# 07-N100.net
KiCad netlist of a schematic drawn in Altium Designer
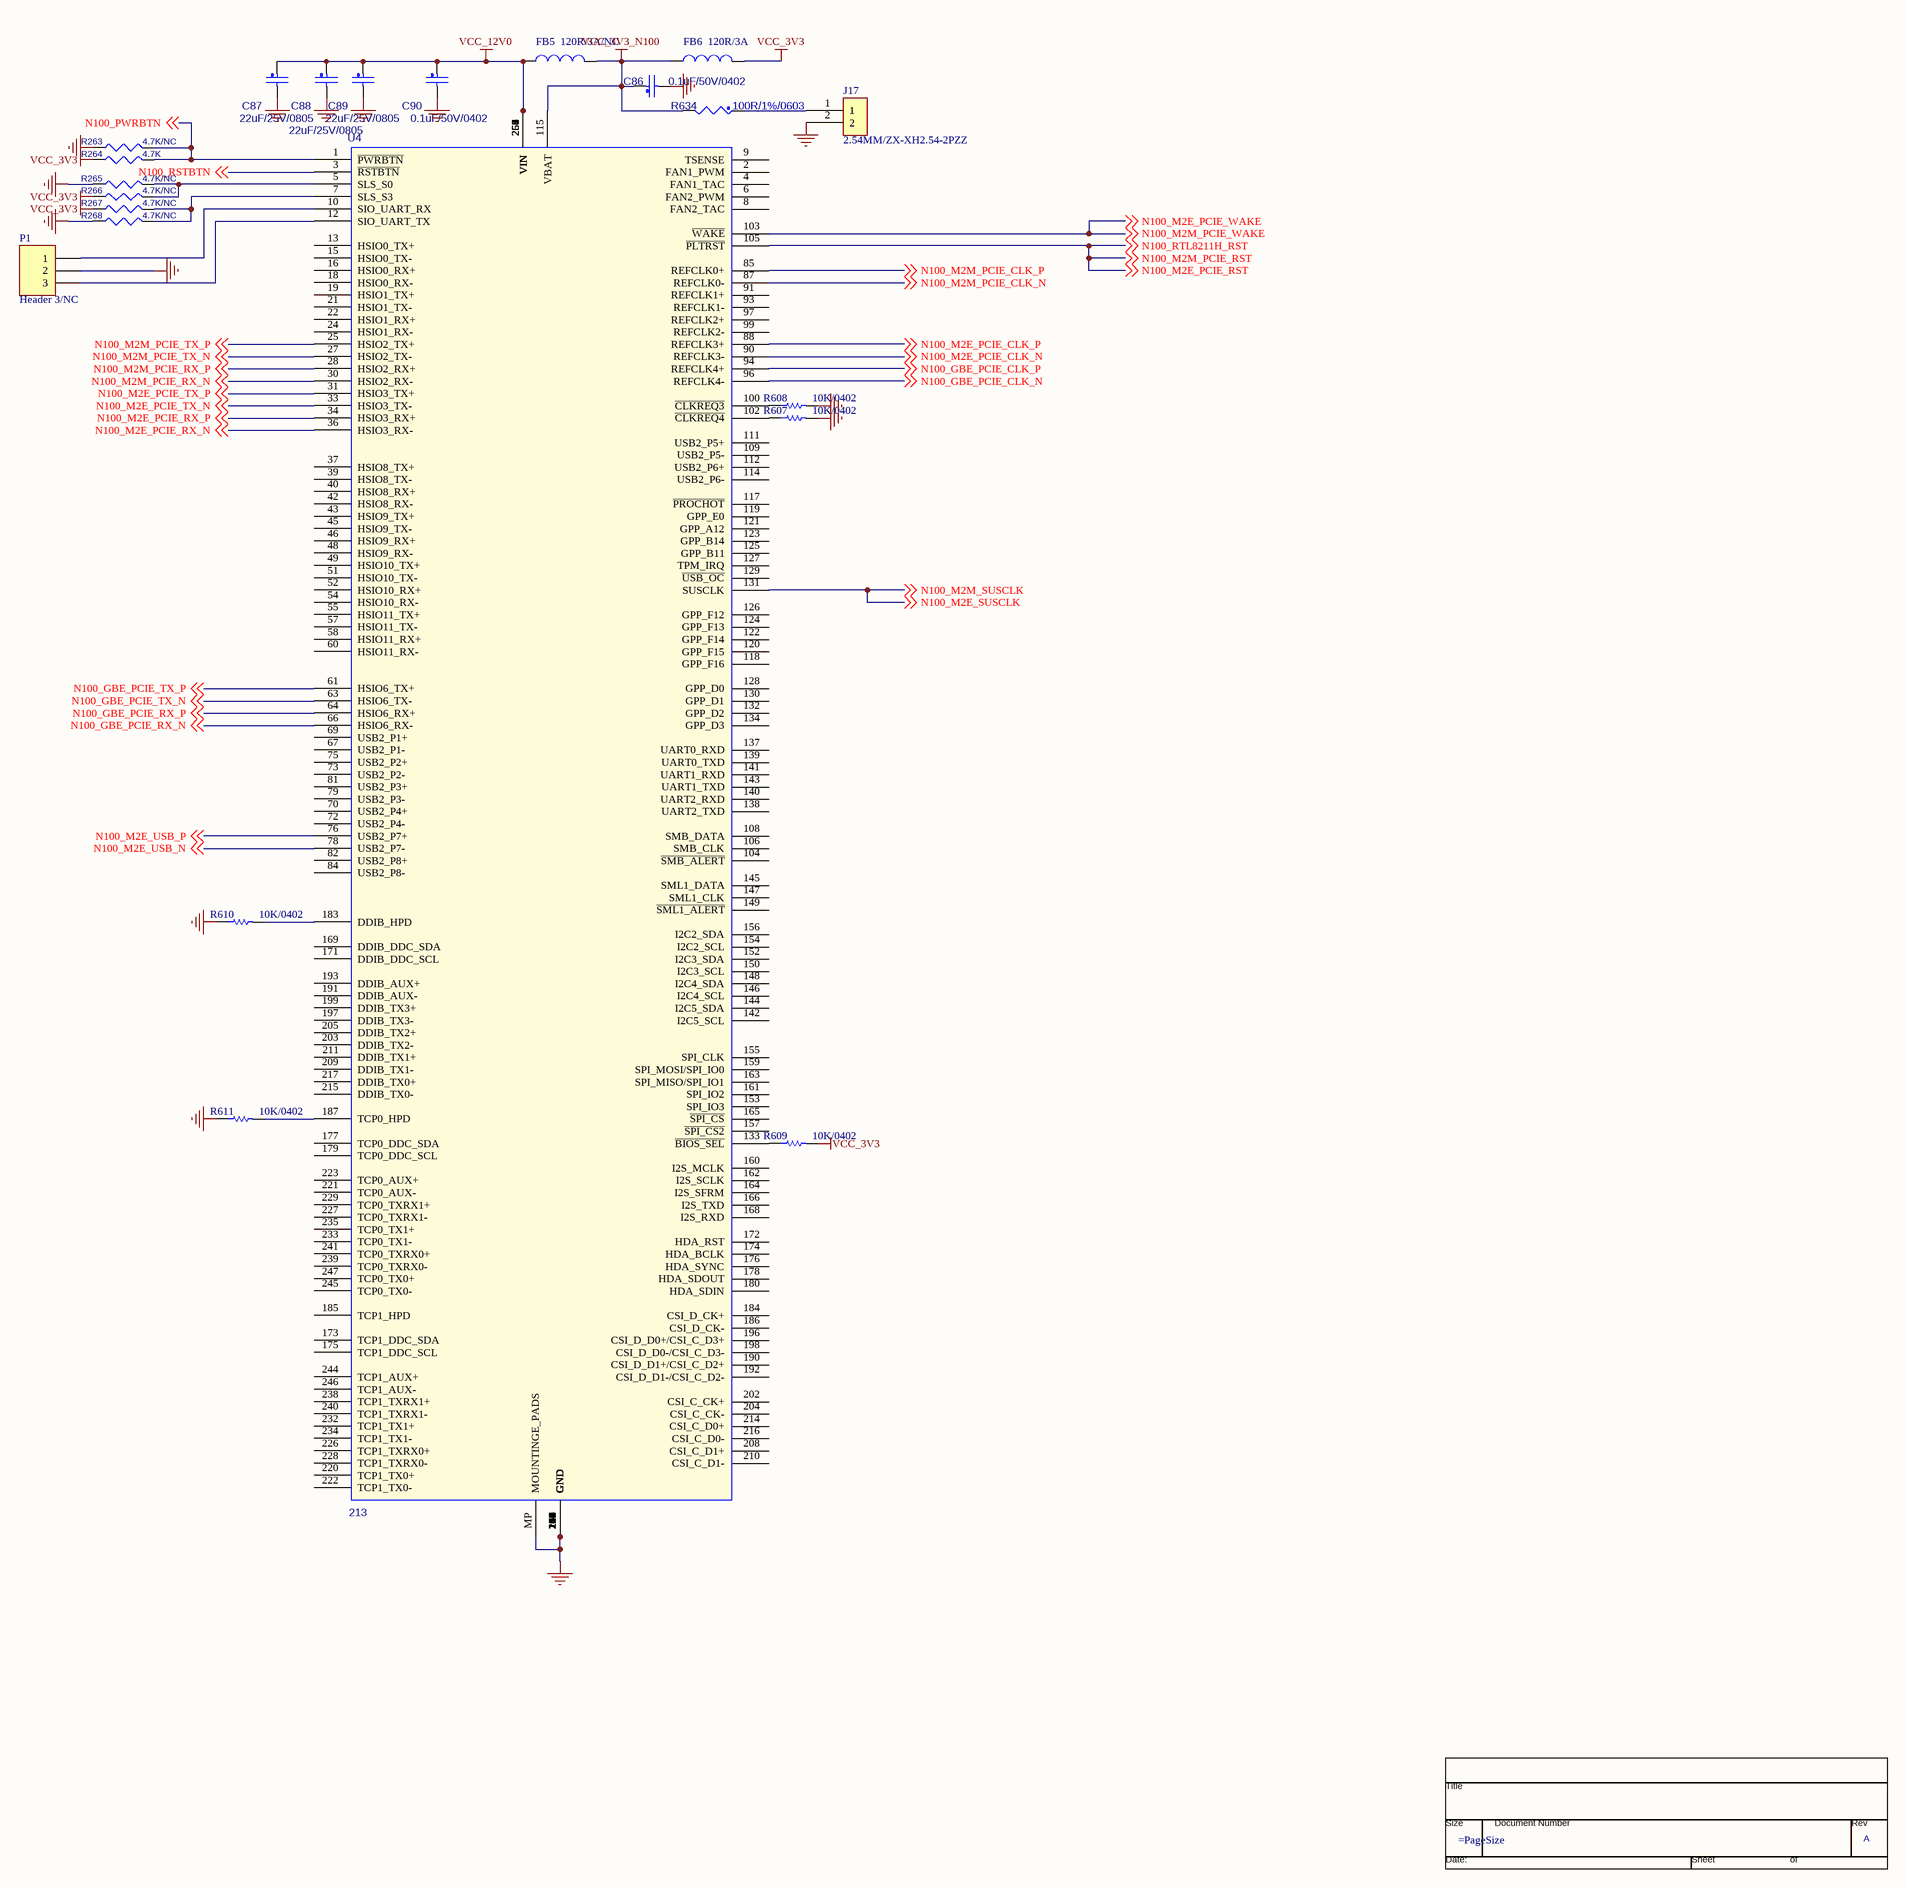
[diagram p0: 07-N100.SchDoc]

(export (version "E")
  (design (tool "Eeschema 10.0.6"))
  (components
    (comp (ref "C86")
      (value "0.1uF/50V/0402")
      (footprint "C0402")
      (description "GCM155R71H104KE02/MURATA")
      (fields (field (name "TOLERANCE") "10%") (field (name "VOLTAGE") "16V"))
      (libsource (lib "*") (part "CAP_NP"))
    )
    (comp (ref "C87")
      (value "22uF/25V/0805")
      (footprint "C0805")
      (description "GRT31CC71E226ME13/MURATA")
      (fields (field (name "VOLTAGE") "10v") (field (name "TOLERANCE") "10%"))
      (libsource (lib "*") (part "CAP_NP"))
    )
    (comp (ref "C88")
      (value "22uF/25V/0805")
      (footprint "C0805")
      (description "GRT31CC71E226ME13/MURATA")
      (fields (field (name "VOLTAGE") "10v") (field (name "TOLERANCE") "10%"))
      (libsource (lib "*") (part "CAP_NP"))
    )
    (comp (ref "C89")
      (value "22uF/25V/0805")
      (footprint "C0805")
      (description "GRT31CC71E226ME13/MURATA")
      (fields (field (name "VOLTAGE") "10v") (field (name "TOLERANCE") "10%"))
      (libsource (lib "*") (part "CAP_NP"))
    )
    (comp (ref "C90")
      (value "0.1uF/50V/0402")
      (footprint "C0402")
      (description "GCM155R71H104KE02/MURATA")
      (fields (field (name "TOLERANCE") "10%") (field (name "VOLTAGE") "16V"))
      (libsource (lib "*") (part "CAP_NP"))
    )
    (comp (ref "FB5")
      (value "120R/3A/NC")
      (footprint "L0603")
      (description "BLM18KG121TN1D")
      (fields (field (name "PUBLISHER") "Altium Limited"))
      (libsource (lib "LIBS") (part "Inductor"))
    )
    (comp (ref "FB6")
      (value "120R/3A")
      (footprint "L0603")
      (description "BLM18KG121TN1D")
      (fields (field (name "PUBLISHER") "Altium Limited"))
      (libsource (lib "LIBS") (part "Inductor"))
    )
    (comp (ref "J17")
      (value "2.54MM/ZX-XH2.54-2PZZ")
      (footprint "CONN-TH_2P-P2.50_HX25003-2A")
      (libsource (lib "LIBS") (part "header2"))
    )
    (comp (ref "P1")
      (value "Header 3/NC")
      (footprint "HEADER3")
      (description "Header, 3-Pin")
      (fields (field (name "PUBLISHER") "Altium Limited"))
      (libsource (lib "LIBS") (part "Header 3"))
    )
    (comp (ref "R263")
      (value "4.7K/NC")
      (footprint "R0402")
      (fields (field (name "Comment") "RESISTOR"))
      (libsource (lib "*") (part "RESISTOR"))
    )
    (comp (ref "R264")
      (value "4.7K")
      (footprint "R0402")
      (fields (field (name "Comment") "RESISTOR"))
      (libsource (lib "*") (part "RESISTOR"))
    )
    (comp (ref "R265")
      (value "4.7K/NC")
      (footprint "R0402")
      (fields (field (name "Comment") "RESISTOR"))
      (libsource (lib "*") (part "RESISTOR"))
    )
    (comp (ref "R266")
      (value "4.7K/NC")
      (footprint "R0402")
      (fields (field (name "Comment") "RESISTOR"))
      (libsource (lib "*") (part "RESISTOR"))
    )
    (comp (ref "R267")
      (value "4.7K/NC")
      (footprint "R0402")
      (fields (field (name "Comment") "RESISTOR"))
      (libsource (lib "*") (part "RESISTOR"))
    )
    (comp (ref "R268")
      (value "4.7K/NC")
      (footprint "R0402")
      (fields (field (name "Comment") "RESISTOR"))
      (libsource (lib "*") (part "RESISTOR"))
    )
    (comp (ref "R607")
      (value "10K/0402")
      (footprint "R0402")
      (description "Semiconductor Resistor")
      (fields (field (name "PUBLISHER") "Altium Limited"))
      (libsource (lib "LIBS") (part "Res Semi"))
    )
    (comp (ref "R608")
      (value "10K/0402")
      (footprint "R0402")
      (description "Semiconductor Resistor")
      (fields (field (name "PUBLISHER") "Altium Limited"))
      (libsource (lib "LIBS") (part "Res Semi"))
    )
    (comp (ref "R609")
      (value "10K/0402")
      (footprint "R0402")
      (description "Semiconductor Resistor")
      (fields (field (name "PUBLISHER") "Altium Limited"))
      (libsource (lib "LIBS") (part "Res Semi"))
    )
    (comp (ref "R610")
      (value "10K/0402")
      (footprint "R0402")
      (description "Semiconductor Resistor")
      (fields (field (name "PUBLISHER") "Altium Limited"))
      (libsource (lib "LIBS") (part "Res Semi"))
    )
    (comp (ref "R611")
      (value "10K/0402")
      (footprint "R0402")
      (description "Semiconductor Resistor")
      (fields (field (name "PUBLISHER") "Altium Limited"))
      (libsource (lib "LIBS") (part "Res Semi"))
    )
    (comp (ref "R634")
      (value "100R/1%/0603")
      (footprint "R0603")
      (description "AC0402FR-070RL/YAGEO")
      (fields (field (name "TOLERANCE") "1%") (field (name "Comment") "RES_Dup2"))
      (libsource (lib "*") (part "RES_Dup2"))
    )
    (comp (ref "U4")
      (value "213")
      (footprint "N100")
      (fields (field (name "Comment") "N100"))
      (libsource (lib "LIBS") (part "N100"))
    )
  )
  (nets
    (net (code "1") (name "GND") (class "Default")
      (node (ref "C86") (pin "2") (pinfunction "2_2") (pintype "passive"))
      (node (ref "C87") (pin "2") (pinfunction "2_2") (pintype "passive"))
      (node (ref "C88") (pin "2") (pinfunction "2_2") (pintype "passive"))
      (node (ref "C89") (pin "2") (pinfunction "2_2") (pintype "passive"))
      (node (ref "C90") (pin "2") (pinfunction "2_2") (pintype "passive"))
      (node (ref "J17") (pin "2") (pinfunction "2_2") (pintype "passive"))
      (node (ref "P1") (pin "2") (pinfunction "2_2") (pintype "passive"))
      (node (ref "R263") (pin "1") (pinfunction "1_1") (pintype "passive"))
      (node (ref "R265") (pin "1") (pinfunction "1_1") (pintype "passive"))
      (node (ref "R268") (pin "1") (pinfunction "1_1") (pintype "passive"))
      (node (ref "R607") (pin "2") (pinfunction "2_2") (pintype "passive"))
      (node (ref "R608") (pin "2") (pinfunction "2_2") (pintype "passive"))
      (node (ref "R610") (pin "1") (pinfunction "1_1") (pintype "passive"))
      (node (ref "R611") (pin "1") (pinfunction "1_1") (pintype "passive"))
      (node (ref "U4") (pin "101") (pinfunction "GND_101") (pintype "passive"))
      (node (ref "U4") (pin "107") (pinfunction "GND_107") (pintype "passive"))
      (node (ref "U4") (pin "11") (pinfunction "GND_11") (pintype "passive"))
      (node (ref "U4") (pin "110") (pinfunction "GND_110") (pintype "passive"))
      (node (ref "U4") (pin "113") (pinfunction "GND_113") (pintype "passive"))
      (node (ref "U4") (pin "116") (pinfunction "GND_116") (pintype "passive"))
      (node (ref "U4") (pin "135") (pinfunction "GND_135") (pintype "passive"))
      (node (ref "U4") (pin "136") (pinfunction "GND_136") (pintype "passive"))
      (node (ref "U4") (pin "14") (pinfunction "GND_14") (pintype "passive"))
      (node (ref "U4") (pin "151") (pinfunction "GND_151") (pintype "passive"))
      (node (ref "U4") (pin "158") (pinfunction "GND_158") (pintype "passive"))
      (node (ref "U4") (pin "167") (pinfunction "GND_167") (pintype "passive"))
      (node (ref "U4") (pin "17") (pinfunction "GND_17") (pintype "passive"))
      (node (ref "U4") (pin "170") (pinfunction "GND_170") (pintype "passive"))
      (node (ref "U4") (pin "181") (pinfunction "GND_181") (pintype "passive"))
      (node (ref "U4") (pin "182") (pinfunction "GND_182") (pintype "passive"))
      (node (ref "U4") (pin "188") (pinfunction "GND_188") (pintype "passive"))
      (node (ref "U4") (pin "189") (pinfunction "GND_189") (pintype "passive"))
      (node (ref "U4") (pin "194") (pinfunction "GND_194") (pintype "passive"))
      (node (ref "U4") (pin "195") (pinfunction "GND_195") (pintype "passive"))
      (node (ref "U4") (pin "20") (pinfunction "GND_20") (pintype "passive"))
      (node (ref "U4") (pin "200") (pinfunction "GND_200") (pintype "passive"))
      (node (ref "U4") (pin "201") (pinfunction "GND_201") (pintype "passive"))
      (node (ref "U4") (pin "206") (pinfunction "GND_206") (pintype "passive"))
      (node (ref "U4") (pin "207") (pinfunction "GND_207") (pintype "passive"))
      (node (ref "U4") (pin "212") (pinfunction "GND_212") (pintype "passive"))
      (node (ref "U4") (pin "213") (pinfunction "GND_213") (pintype "passive"))
      (node (ref "U4") (pin "218") (pinfunction "GND_218") (pintype "passive"))
      (node (ref "U4") (pin "219") (pinfunction "GND_219") (pintype "passive"))
      (node (ref "U4") (pin "224") (pinfunction "GND_224") (pintype "passive"))
      (node (ref "U4") (pin "225") (pinfunction "GND_225") (pintype "passive"))
      (node (ref "U4") (pin "23") (pinfunction "GND_23") (pintype "passive"))
      (node (ref "U4") (pin "230") (pinfunction "GND_230") (pintype "passive"))
      (node (ref "U4") (pin "231") (pinfunction "GND_231") (pintype "passive"))
      (node (ref "U4") (pin "236") (pinfunction "GND_236") (pintype "passive"))
      (node (ref "U4") (pin "237") (pinfunction "GND_237") (pintype "passive"))
      (node (ref "U4") (pin "242") (pinfunction "GND_242") (pintype "passive"))
      (node (ref "U4") (pin "243") (pinfunction "GND_243") (pintype "passive"))
      (node (ref "U4") (pin "248") (pinfunction "GND_248") (pintype "passive"))
      (node (ref "U4") (pin "249") (pinfunction "GND_249") (pintype "passive"))
      (node (ref "U4") (pin "26") (pinfunction "GND_26") (pintype "passive"))
      (node (ref "U4") (pin "29") (pinfunction "GND_29") (pintype "passive"))
      (node (ref "U4") (pin "32") (pinfunction "GND_32") (pintype "passive"))
      (node (ref "U4") (pin "35") (pinfunction "GND_35") (pintype "passive"))
      (node (ref "U4") (pin "38") (pinfunction "GND_38") (pintype "passive"))
      (node (ref "U4") (pin "41") (pinfunction "GND_41") (pintype "passive"))
      (node (ref "U4") (pin "44") (pinfunction "GND_44") (pintype "passive"))
      (node (ref "U4") (pin "47") (pinfunction "GND_47") (pintype "passive"))
      (node (ref "U4") (pin "50") (pinfunction "GND_50") (pintype "passive"))
      (node (ref "U4") (pin "53") (pinfunction "GND_53") (pintype "passive"))
      (node (ref "U4") (pin "56") (pinfunction "GND_56") (pintype "passive"))
      (node (ref "U4") (pin "59") (pinfunction "GND_59") (pintype "passive"))
      (node (ref "U4") (pin "62") (pinfunction "GND_62") (pintype "passive"))
      (node (ref "U4") (pin "65") (pinfunction "GND_65") (pintype "passive"))
      (node (ref "U4") (pin "68") (pinfunction "GND_68") (pintype "passive"))
      (node (ref "U4") (pin "71") (pinfunction "GND_71") (pintype "passive"))
      (node (ref "U4") (pin "74") (pinfunction "GND_74") (pintype "passive"))
      (node (ref "U4") (pin "77") (pinfunction "GND_77") (pintype "passive"))
      (node (ref "U4") (pin "80") (pinfunction "GND_80") (pintype "passive"))
      (node (ref "U4") (pin "83") (pinfunction "GND_83") (pintype "passive"))
      (node (ref "U4") (pin "86") (pinfunction "GND_86") (pintype "passive"))
      (node (ref "U4") (pin "89") (pinfunction "GND_89") (pintype "passive"))
      (node (ref "U4") (pin "92") (pinfunction "GND_92") (pintype "passive"))
      (node (ref "U4") (pin "95") (pinfunction "GND_95") (pintype "passive"))
      (node (ref "U4") (pin "98") (pinfunction "GND_98") (pintype "passive"))
      (node (ref "U4") (pin "MP") (pinfunction "MOUNTINGE_PADS_MP") (pintype "passive"))
    )
    (net (code "2") (name "N100_GBE_PCIE_CLK_N") (class "Default")
      (node (ref "U4") (pin "96") (pinfunction "REFCLK4-_96") (pintype "passive"))
    )
    (net (code "3") (name "N100_GBE_PCIE_CLK_P") (class "Default")
      (node (ref "U4") (pin "94") (pinfunction "REFCLK4+_94") (pintype "passive"))
    )
    (net (code "4") (name "N100_GBE_PCIE_RX_N") (class "Default")
      (node (ref "U4") (pin "66") (pinfunction "HSIO6_RX-_66") (pintype "passive"))
    )
    (net (code "5") (name "N100_GBE_PCIE_RX_P") (class "Default")
      (node (ref "U4") (pin "64") (pinfunction "HSIO6_RX+_64") (pintype "passive"))
    )
    (net (code "6") (name "N100_GBE_PCIE_TX_N") (class "Default")
      (node (ref "U4") (pin "63") (pinfunction "HSIO6_TX-_63") (pintype "passive"))
    )
    (net (code "7") (name "N100_GBE_PCIE_TX_P") (class "Default")
      (node (ref "U4") (pin "61") (pinfunction "HSIO6_TX+_61") (pintype "passive"))
    )
    (net (code "8") (name "N100_M2E_PCIE_CLK_N") (class "Default")
      (node (ref "U4") (pin "90") (pinfunction "REFCLK3-_90") (pintype "passive"))
    )
    (net (code "9") (name "N100_M2E_PCIE_CLK_P") (class "Default")
      (node (ref "U4") (pin "88") (pinfunction "REFCLK3+_88") (pintype "passive"))
    )
    (net (code "10") (name "N100_M2E_PCIE_RST") (class "Default")
      (node (ref "U4") (pin "105") (pinfunction "~{PLTRST}_105") (pintype "passive"))
    )
    (net (code "11") (name "N100_M2E_PCIE_RX_N") (class "Default")
      (node (ref "U4") (pin "36") (pinfunction "HSIO3_RX-_36") (pintype "passive"))
    )
    (net (code "12") (name "N100_M2E_PCIE_RX_P") (class "Default")
      (node (ref "U4") (pin "34") (pinfunction "HSIO3_RX+_34") (pintype "passive"))
    )
    (net (code "13") (name "N100_M2E_PCIE_TX_N") (class "Default")
      (node (ref "U4") (pin "33") (pinfunction "HSIO3_TX-_33") (pintype "passive"))
    )
    (net (code "14") (name "N100_M2E_PCIE_TX_P") (class "Default")
      (node (ref "U4") (pin "31") (pinfunction "HSIO3_TX+_31") (pintype "passive"))
    )
    (net (code "15") (name "N100_M2E_PCIE_WAKE") (class "Default")
      (node (ref "U4") (pin "103") (pinfunction "~{WAKE}_103") (pintype "passive"))
    )
    (net (code "16") (name "N100_M2E_SUSCLK") (class "Default")
      (node (ref "U4") (pin "131") (pinfunction "SUSCLK_131") (pintype "passive"))
    )
    (net (code "17") (name "N100_M2E_USB_N") (class "Default")
      (node (ref "U4") (pin "78") (pinfunction "USB2_P7-_78") (pintype "passive"))
    )
    (net (code "18") (name "N100_M2E_USB_P") (class "Default")
      (node (ref "U4") (pin "76") (pinfunction "USB2_P7+_76") (pintype "passive"))
    )
    (net (code "19") (name "N100_M2M_PCIE_CLK_N") (class "Default")
      (node (ref "U4") (pin "87") (pinfunction "REFCLK0-_87") (pintype "passive"))
    )
    (net (code "20") (name "N100_M2M_PCIE_CLK_P") (class "Default")
      (node (ref "U4") (pin "85") (pinfunction "REFCLK0+_85") (pintype "passive"))
    )
    (net (code "21") (name "N100_M2M_PCIE_RX_N") (class "Default")
      (node (ref "U4") (pin "30") (pinfunction "HSIO2_RX-_30") (pintype "passive"))
    )
    (net (code "22") (name "N100_M2M_PCIE_RX_P") (class "Default")
      (node (ref "U4") (pin "28") (pinfunction "HSIO2_RX+_28") (pintype "passive"))
    )
    (net (code "23") (name "N100_M2M_PCIE_TX_N") (class "Default")
      (node (ref "U4") (pin "27") (pinfunction "HSIO2_TX-_27") (pintype "passive"))
    )
    (net (code "24") (name "N100_M2M_PCIE_TX_P") (class "Default")
      (node (ref "U4") (pin "25") (pinfunction "HSIO2_TX+_25") (pintype "passive"))
    )
    (net (code "25") (name "N100_PWRBTN") (class "Default")
      (node (ref "R263") (pin "2") (pinfunction "2_2") (pintype "passive"))
      (node (ref "R264") (pin "2") (pinfunction "2_2") (pintype "passive"))
      (node (ref "U4") (pin "1") (pinfunction "~{PWRBTN}_1") (pintype "passive"))
    )
    (net (code "26") (name "N100_RSTBTN") (class "Default")
      (node (ref "U4") (pin "3") (pinfunction "~{RSTBTN}_3") (pintype "passive"))
    )
    (net (code "27") (name "Net-(J17-Pad1)") (class "Default")
      (node (ref "J17") (pin "1") (pinfunction "1_1") (pintype "passive"))
      (node (ref "R634") (pin "1") (pinfunction "1_1") (pintype "passive"))
    )
    (net (code "28") (name "Net-(U4-DDIB_HPD)") (class "Default")
      (node (ref "R610") (pin "2") (pinfunction "2_2") (pintype "passive"))
      (node (ref "U4") (pin "183") (pinfunction "DDIB_HPD_183") (pintype "passive"))
    )
    (net (code "29") (name "Net-(U4-SIO_UART_RX)") (class "Default")
      (node (ref "P1") (pin "1") (pinfunction "1_1") (pintype "passive"))
      (node (ref "U4") (pin "10") (pinfunction "SIO_UART_RX_10") (pintype "passive"))
    )
    (net (code "30") (name "Net-(U4-SIO_UART_TX)") (class "Default")
      (node (ref "P1") (pin "3") (pinfunction "3_3") (pintype "passive"))
      (node (ref "U4") (pin "12") (pinfunction "SIO_UART_TX_12") (pintype "passive"))
    )
    (net (code "31") (name "Net-(U4-SLS_S0)") (class "Default")
      (node (ref "R265") (pin "2") (pinfunction "2_2") (pintype "passive"))
      (node (ref "R266") (pin "2") (pinfunction "2_2") (pintype "passive"))
      (node (ref "U4") (pin "5") (pinfunction "SLS_S0_5") (pintype "passive"))
    )
    (net (code "32") (name "Net-(U4-SLS_S3)") (class "Default")
      (node (ref "R267") (pin "2") (pinfunction "2_2") (pintype "passive"))
      (node (ref "R268") (pin "2") (pinfunction "2_2") (pintype "passive"))
      (node (ref "U4") (pin "7") (pinfunction "SLS_S3_7") (pintype "passive"))
    )
    (net (code "33") (name "Net-(U4-TCP0_HPD)") (class "Default")
      (node (ref "R611") (pin "2") (pinfunction "2_2") (pintype "passive"))
      (node (ref "U4") (pin "187") (pinfunction "TCP0_HPD_187") (pintype "passive"))
    )
    (net (code "34") (name "Net-(U4-~{BIOS_SEL})") (class "Default")
      (node (ref "R609") (pin "1") (pinfunction "1_1") (pintype "passive"))
      (node (ref "U4") (pin "133") (pinfunction "~{BIOS_SEL}_133") (pintype "passive"))
    )
    (net (code "35") (name "Net-(U4-~{CLKREQ3})") (class "Default")
      (node (ref "R608") (pin "1") (pinfunction "1_1") (pintype "passive"))
      (node (ref "U4") (pin "100") (pinfunction "~{CLKREQ3}_100") (pintype "passive"))
    )
    (net (code "36") (name "Net-(U4-~{CLKREQ4})") (class "Default")
      (node (ref "R607") (pin "1") (pinfunction "1_1") (pintype "passive"))
      (node (ref "U4") (pin "102") (pinfunction "~{CLKREQ4}_102") (pintype "passive"))
    )
    (net (code "37") (name "VCC_3V3") (class "Default")
      (node (ref "FB6") (pin "2") (pinfunction "2_2") (pintype "passive"))
      (node (ref "R264") (pin "1") (pinfunction "1_1") (pintype "passive"))
      (node (ref "R266") (pin "1") (pinfunction "1_1") (pintype "passive"))
      (node (ref "R267") (pin "1") (pinfunction "1_1") (pintype "passive"))
      (node (ref "R609") (pin "2") (pinfunction "2_2") (pintype "passive"))
    )
    (net (code "38") (name "VCC_3V3_N100") (class "Default")
      (node (ref "C86") (pin "1") (pinfunction "1_1") (pintype "passive"))
      (node (ref "FB5") (pin "2") (pinfunction "2_2") (pintype "passive"))
      (node (ref "FB6") (pin "1") (pinfunction "1_1") (pintype "passive"))
      (node (ref "R634") (pin "2") (pinfunction "2_2") (pintype "passive"))
      (node (ref "U4") (pin "115") (pinfunction "VBAT_115") (pintype "passive"))
    )
    (net (code "39") (name "VCC_12V0") (class "Default")
      (node (ref "C87") (pin "1") (pinfunction "1_1") (pintype "passive"))
      (node (ref "C88") (pin "1") (pinfunction "1_1") (pintype "passive"))
      (node (ref "C89") (pin "1") (pinfunction "1_1") (pintype "passive"))
      (node (ref "C90") (pin "1") (pinfunction "1_1") (pintype "passive"))
      (node (ref "FB5") (pin "1") (pinfunction "1_1") (pintype "passive"))
      (node (ref "U4") (pin "250") (pinfunction "VIN_250") (pintype "passive"))
      (node (ref "U4") (pin "251") (pinfunction "VIN_251") (pintype "passive"))
      (node (ref "U4") (pin "252") (pinfunction "VIN_252") (pintype "passive"))
      (node (ref "U4") (pin "253") (pinfunction "VIN_253") (pintype "passive"))
      (node (ref "U4") (pin "254") (pinfunction "VIN_254") (pintype "passive"))
      (node (ref "U4") (pin "255") (pinfunction "VIN_255") (pintype "passive"))
      (node (ref "U4") (pin "256") (pinfunction "VIN_256") (pintype "passive"))
      (node (ref "U4") (pin "257") (pinfunction "VIN_257") (pintype "passive"))
      (node (ref "U4") (pin "258") (pinfunction "VIN_258") (pintype "passive"))
      (node (ref "U4") (pin "259") (pinfunction "VIN_259") (pintype "passive"))
      (node (ref "U4") (pin "260") (pinfunction "VIN_260") (pintype "passive"))
    )
    (net (code "40") (name "unconnected-(U4-CSI_C_CK+-Pad202)") (class "Default")
      (node (ref "U4") (pin "202") (pinfunction "CSI_C_CK+_202") (pintype "passive"))
    )
    (net (code "41") (name "unconnected-(U4-CSI_C_CK--Pad204)") (class "Default")
      (node (ref "U4") (pin "204") (pinfunction "CSI_C_CK-_204") (pintype "passive"))
    )
    (net (code "42") (name "unconnected-(U4-CSI_C_D0+-Pad214)") (class "Default")
      (node (ref "U4") (pin "214") (pinfunction "CSI_C_D0+_214") (pintype "passive"))
    )
    (net (code "43") (name "unconnected-(U4-CSI_C_D0--Pad216)") (class "Default")
      (node (ref "U4") (pin "216") (pinfunction "CSI_C_D0-_216") (pintype "passive"))
    )
    (net (code "44") (name "unconnected-(U4-CSI_C_D1+-Pad208)") (class "Default")
      (node (ref "U4") (pin "208") (pinfunction "CSI_C_D1+_208") (pintype "passive"))
    )
    (net (code "45") (name "unconnected-(U4-CSI_C_D1--Pad210)") (class "Default")
      (node (ref "U4") (pin "210") (pinfunction "CSI_C_D1-_210") (pintype "passive"))
    )
    (net (code "46") (name "unconnected-(U4-CSI_D_CK+-Pad184)") (class "Default")
      (node (ref "U4") (pin "184") (pinfunction "CSI_D_CK+_184") (pintype "passive"))
    )
    (net (code "47") (name "unconnected-(U4-CSI_D_CK--Pad186)") (class "Default")
      (node (ref "U4") (pin "186") (pinfunction "CSI_D_CK-_186") (pintype "passive"))
    )
    (net (code "48") (name "unconnected-(U4-CSI_D_D0+{slash}CSI_C_D3+-Pad196)") (class "Default")
      (node (ref "U4") (pin "196") (pinfunction "CSI_D_D0+/CSI_C_D3+_196") (pintype "passive"))
    )
    (net (code "49") (name "unconnected-(U4-CSI_D_D0-{slash}CSI_C_D3--Pad198)") (class "Default")
      (node (ref "U4") (pin "198") (pinfunction "CSI_D_D0-/CSI_C_D3-_198") (pintype "passive"))
    )
    (net (code "50") (name "unconnected-(U4-CSI_D_D1+{slash}CSI_C_D2+-Pad190)") (class "Default")
      (node (ref "U4") (pin "190") (pinfunction "CSI_D_D1+/CSI_C_D2+_190") (pintype "passive"))
    )
    (net (code "51") (name "unconnected-(U4-CSI_D_D1-{slash}CSI_C_D2--Pad192)") (class "Default")
      (node (ref "U4") (pin "192") (pinfunction "CSI_D_D1-/CSI_C_D2-_192") (pintype "passive"))
    )
    (net (code "52") (name "unconnected-(U4-DDIB_AUX+-Pad193)") (class "Default")
      (node (ref "U4") (pin "193") (pinfunction "DDIB_AUX+_193") (pintype "passive"))
    )
    (net (code "53") (name "unconnected-(U4-DDIB_AUX--Pad191)") (class "Default")
      (node (ref "U4") (pin "191") (pinfunction "DDIB_AUX-_191") (pintype "passive"))
    )
    (net (code "54") (name "unconnected-(U4-DDIB_DDC_SCL-Pad171)") (class "Default")
      (node (ref "U4") (pin "171") (pinfunction "DDIB_DDC_SCL_171") (pintype "passive"))
    )
    (net (code "55") (name "unconnected-(U4-DDIB_DDC_SDA-Pad169)") (class "Default")
      (node (ref "U4") (pin "169") (pinfunction "DDIB_DDC_SDA_169") (pintype "passive"))
    )
    (net (code "56") (name "unconnected-(U4-DDIB_TX0+-Pad217)") (class "Default")
      (node (ref "U4") (pin "217") (pinfunction "DDIB_TX0+_217") (pintype "passive"))
    )
    (net (code "57") (name "unconnected-(U4-DDIB_TX0--Pad215)") (class "Default")
      (node (ref "U4") (pin "215") (pinfunction "DDIB_TX0-_215") (pintype "passive"))
    )
    (net (code "58") (name "unconnected-(U4-DDIB_TX1+-Pad211)") (class "Default")
      (node (ref "U4") (pin "211") (pinfunction "DDIB_TX1+_211") (pintype "passive"))
    )
    (net (code "59") (name "unconnected-(U4-DDIB_TX1--Pad209)") (class "Default")
      (node (ref "U4") (pin "209") (pinfunction "DDIB_TX1-_209") (pintype "passive"))
    )
    (net (code "60") (name "unconnected-(U4-DDIB_TX2+-Pad205)") (class "Default")
      (node (ref "U4") (pin "205") (pinfunction "DDIB_TX2+_205") (pintype "passive"))
    )
    (net (code "61") (name "unconnected-(U4-DDIB_TX2--Pad203)") (class "Default")
      (node (ref "U4") (pin "203") (pinfunction "DDIB_TX2-_203") (pintype "passive"))
    )
    (net (code "62") (name "unconnected-(U4-DDIB_TX3+-Pad199)") (class "Default")
      (node (ref "U4") (pin "199") (pinfunction "DDIB_TX3+_199") (pintype "passive"))
    )
    (net (code "63") (name "unconnected-(U4-DDIB_TX3--Pad197)") (class "Default")
      (node (ref "U4") (pin "197") (pinfunction "DDIB_TX3-_197") (pintype "passive"))
    )
    (net (code "64") (name "unconnected-(U4-FAN1_PWM-Pad2)") (class "Default")
      (node (ref "U4") (pin "2") (pinfunction "FAN1_PWM_2") (pintype "passive"))
    )
    (net (code "65") (name "unconnected-(U4-FAN1_TAC-Pad4)") (class "Default")
      (node (ref "U4") (pin "4") (pinfunction "FAN1_TAC_4") (pintype "passive"))
    )
    (net (code "66") (name "unconnected-(U4-FAN2_PWM-Pad6)") (class "Default")
      (node (ref "U4") (pin "6") (pinfunction "FAN2_PWM_6") (pintype "passive"))
    )
    (net (code "67") (name "unconnected-(U4-FAN2_TAC-Pad8)") (class "Default")
      (node (ref "U4") (pin "8") (pinfunction "FAN2_TAC_8") (pintype "passive"))
    )
    (net (code "68") (name "unconnected-(U4-GPP_A12-Pad121)") (class "Default")
      (node (ref "U4") (pin "121") (pinfunction "GPP_A12_121") (pintype "passive"))
    )
    (net (code "69") (name "unconnected-(U4-GPP_B11-Pad125)") (class "Default")
      (node (ref "U4") (pin "125") (pinfunction "GPP_B11_125") (pintype "passive"))
    )
    (net (code "70") (name "unconnected-(U4-GPP_B14-Pad123)") (class "Default")
      (node (ref "U4") (pin "123") (pinfunction "GPP_B14_123") (pintype "passive"))
    )
    (net (code "71") (name "unconnected-(U4-GPP_D0-Pad128)") (class "Default")
      (node (ref "U4") (pin "128") (pinfunction "GPP_D0_128") (pintype "passive"))
    )
    (net (code "72") (name "unconnected-(U4-GPP_D1-Pad130)") (class "Default")
      (node (ref "U4") (pin "130") (pinfunction "GPP_D1_130") (pintype "passive"))
    )
    (net (code "73") (name "unconnected-(U4-GPP_D2-Pad132)") (class "Default")
      (node (ref "U4") (pin "132") (pinfunction "GPP_D2_132") (pintype "passive"))
    )
    (net (code "74") (name "unconnected-(U4-GPP_D3-Pad134)") (class "Default")
      (node (ref "U4") (pin "134") (pinfunction "GPP_D3_134") (pintype "passive"))
    )
    (net (code "75") (name "unconnected-(U4-GPP_E0-Pad119)") (class "Default")
      (node (ref "U4") (pin "119") (pinfunction "GPP_E0_119") (pintype "passive"))
    )
    (net (code "76") (name "unconnected-(U4-GPP_F12-Pad126)") (class "Default")
      (node (ref "U4") (pin "126") (pinfunction "GPP_F12_126") (pintype "passive"))
    )
    (net (code "77") (name "unconnected-(U4-GPP_F13-Pad124)") (class "Default")
      (node (ref "U4") (pin "124") (pinfunction "GPP_F13_124") (pintype "passive"))
    )
    (net (code "78") (name "unconnected-(U4-GPP_F14-Pad122)") (class "Default")
      (node (ref "U4") (pin "122") (pinfunction "GPP_F14_122") (pintype "passive"))
    )
    (net (code "79") (name "unconnected-(U4-GPP_F15-Pad120)") (class "Default")
      (node (ref "U4") (pin "120") (pinfunction "GPP_F15_120") (pintype "passive"))
    )
    (net (code "80") (name "unconnected-(U4-GPP_F16-Pad118)") (class "Default")
      (node (ref "U4") (pin "118") (pinfunction "GPP_F16_118") (pintype "passive"))
    )
    (net (code "81") (name "unconnected-(U4-HDA_BCLK-Pad174)") (class "Default")
      (node (ref "U4") (pin "174") (pinfunction "HDA_BCLK_174") (pintype "passive"))
    )
    (net (code "82") (name "unconnected-(U4-HDA_RST-Pad172)") (class "Default")
      (node (ref "U4") (pin "172") (pinfunction "HDA_RST_172") (pintype "passive"))
    )
    (net (code "83") (name "unconnected-(U4-HDA_SDIN-Pad180)") (class "Default")
      (node (ref "U4") (pin "180") (pinfunction "HDA_SDIN_180") (pintype "passive"))
    )
    (net (code "84") (name "unconnected-(U4-HDA_SDOUT-Pad178)") (class "Default")
      (node (ref "U4") (pin "178") (pinfunction "HDA_SDOUT_178") (pintype "passive"))
    )
    (net (code "85") (name "unconnected-(U4-HDA_SYNC-Pad176)") (class "Default")
      (node (ref "U4") (pin "176") (pinfunction "HDA_SYNC_176") (pintype "passive"))
    )
    (net (code "86") (name "unconnected-(U4-HSIO0_RX+-Pad16)") (class "Default")
      (node (ref "U4") (pin "16") (pinfunction "HSIO0_RX+_16") (pintype "passive"))
    )
    (net (code "87") (name "unconnected-(U4-HSIO0_RX--Pad18)") (class "Default")
      (node (ref "U4") (pin "18") (pinfunction "HSIO0_RX-_18") (pintype "passive"))
    )
    (net (code "88") (name "unconnected-(U4-HSIO0_TX+-Pad13)") (class "Default")
      (node (ref "U4") (pin "13") (pinfunction "HSIO0_TX+_13") (pintype "passive"))
    )
    (net (code "89") (name "unconnected-(U4-HSIO0_TX--Pad15)") (class "Default")
      (node (ref "U4") (pin "15") (pinfunction "HSIO0_TX-_15") (pintype "passive"))
    )
    (net (code "90") (name "unconnected-(U4-HSIO1_RX+-Pad22)") (class "Default")
      (node (ref "U4") (pin "22") (pinfunction "HSIO1_RX+_22") (pintype "passive"))
    )
    (net (code "91") (name "unconnected-(U4-HSIO1_RX--Pad24)") (class "Default")
      (node (ref "U4") (pin "24") (pinfunction "HSIO1_RX-_24") (pintype "passive"))
    )
    (net (code "92") (name "unconnected-(U4-HSIO1_TX+-Pad19)") (class "Default")
      (node (ref "U4") (pin "19") (pinfunction "HSIO1_TX+_19") (pintype "passive"))
    )
    (net (code "93") (name "unconnected-(U4-HSIO1_TX--Pad21)") (class "Default")
      (node (ref "U4") (pin "21") (pinfunction "HSIO1_TX-_21") (pintype "passive"))
    )
    (net (code "94") (name "unconnected-(U4-HSIO8_RX+-Pad40)") (class "Default")
      (node (ref "U4") (pin "40") (pinfunction "HSIO8_RX+_40") (pintype "passive"))
    )
    (net (code "95") (name "unconnected-(U4-HSIO8_RX--Pad42)") (class "Default")
      (node (ref "U4") (pin "42") (pinfunction "HSIO8_RX-_42") (pintype "passive"))
    )
    (net (code "96") (name "unconnected-(U4-HSIO8_TX+-Pad37)") (class "Default")
      (node (ref "U4") (pin "37") (pinfunction "HSIO8_TX+_37") (pintype "passive"))
    )
    (net (code "97") (name "unconnected-(U4-HSIO8_TX--Pad39)") (class "Default")
      (node (ref "U4") (pin "39") (pinfunction "HSIO8_TX-_39") (pintype "passive"))
    )
    (net (code "98") (name "unconnected-(U4-HSIO9_RX+-Pad46)") (class "Default")
      (node (ref "U4") (pin "46") (pinfunction "HSIO9_RX+_46") (pintype "passive"))
    )
    (net (code "99") (name "unconnected-(U4-HSIO9_RX--Pad48)") (class "Default")
      (node (ref "U4") (pin "48") (pinfunction "HSIO9_RX-_48") (pintype "passive"))
    )
    (net (code "100") (name "unconnected-(U4-HSIO9_TX+-Pad43)") (class "Default")
      (node (ref "U4") (pin "43") (pinfunction "HSIO9_TX+_43") (pintype "passive"))
    )
    (net (code "101") (name "unconnected-(U4-HSIO9_TX--Pad45)") (class "Default")
      (node (ref "U4") (pin "45") (pinfunction "HSIO9_TX-_45") (pintype "passive"))
    )
    (net (code "102") (name "unconnected-(U4-HSIO10_RX+-Pad52)") (class "Default")
      (node (ref "U4") (pin "52") (pinfunction "HSIO10_RX+_52") (pintype "passive"))
    )
    (net (code "103") (name "unconnected-(U4-HSIO10_RX--Pad54)") (class "Default")
      (node (ref "U4") (pin "54") (pinfunction "HSIO10_RX-_54") (pintype "passive"))
    )
    (net (code "104") (name "unconnected-(U4-HSIO10_TX+-Pad49)") (class "Default")
      (node (ref "U4") (pin "49") (pinfunction "HSIO10_TX+_49") (pintype "passive"))
    )
    (net (code "105") (name "unconnected-(U4-HSIO10_TX--Pad51)") (class "Default")
      (node (ref "U4") (pin "51") (pinfunction "HSIO10_TX-_51") (pintype "passive"))
    )
    (net (code "106") (name "unconnected-(U4-HSIO11_RX+-Pad58)") (class "Default")
      (node (ref "U4") (pin "58") (pinfunction "HSIO11_RX+_58") (pintype "passive"))
    )
    (net (code "107") (name "unconnected-(U4-HSIO11_RX--Pad60)") (class "Default")
      (node (ref "U4") (pin "60") (pinfunction "HSIO11_RX-_60") (pintype "passive"))
    )
    (net (code "108") (name "unconnected-(U4-HSIO11_TX+-Pad55)") (class "Default")
      (node (ref "U4") (pin "55") (pinfunction "HSIO11_TX+_55") (pintype "passive"))
    )
    (net (code "109") (name "unconnected-(U4-HSIO11_TX--Pad57)") (class "Default")
      (node (ref "U4") (pin "57") (pinfunction "HSIO11_TX-_57") (pintype "passive"))
    )
    (net (code "110") (name "unconnected-(U4-I2C2_SCL-Pad154)") (class "Default")
      (node (ref "U4") (pin "154") (pinfunction "I2C2_SCL_154") (pintype "passive"))
    )
    (net (code "111") (name "unconnected-(U4-I2C2_SDA-Pad156)") (class "Default")
      (node (ref "U4") (pin "156") (pinfunction "I2C2_SDA_156") (pintype "passive"))
    )
    (net (code "112") (name "unconnected-(U4-I2C3_SCL-Pad150)") (class "Default")
      (node (ref "U4") (pin "150") (pinfunction "I2C3_SCL_150") (pintype "passive"))
    )
    (net (code "113") (name "unconnected-(U4-I2C3_SDA-Pad152)") (class "Default")
      (node (ref "U4") (pin "152") (pinfunction "I2C3_SDA_152") (pintype "passive"))
    )
    (net (code "114") (name "unconnected-(U4-I2C4_SCL-Pad146)") (class "Default")
      (node (ref "U4") (pin "146") (pinfunction "I2C4_SCL_146") (pintype "passive"))
    )
    (net (code "115") (name "unconnected-(U4-I2C4_SDA-Pad148)") (class "Default")
      (node (ref "U4") (pin "148") (pinfunction "I2C4_SDA_148") (pintype "passive"))
    )
    (net (code "116") (name "unconnected-(U4-I2C5_SCL-Pad142)") (class "Default")
      (node (ref "U4") (pin "142") (pinfunction "I2C5_SCL_142") (pintype "passive"))
    )
    (net (code "117") (name "unconnected-(U4-I2C5_SDA-Pad144)") (class "Default")
      (node (ref "U4") (pin "144") (pinfunction "I2C5_SDA_144") (pintype "passive"))
    )
    (net (code "118") (name "unconnected-(U4-I2S_MCLK-Pad160)") (class "Default")
      (node (ref "U4") (pin "160") (pinfunction "I2S_MCLK_160") (pintype "passive"))
    )
    (net (code "119") (name "unconnected-(U4-I2S_RXD-Pad168)") (class "Default")
      (node (ref "U4") (pin "168") (pinfunction "I2S_RXD_168") (pintype "passive"))
    )
    (net (code "120") (name "unconnected-(U4-I2S_SCLK-Pad162)") (class "Default")
      (node (ref "U4") (pin "162") (pinfunction "I2S_SCLK_162") (pintype "passive"))
    )
    (net (code "121") (name "unconnected-(U4-I2S_SFRM-Pad164)") (class "Default")
      (node (ref "U4") (pin "164") (pinfunction "I2S_SFRM_164") (pintype "passive"))
    )
    (net (code "122") (name "unconnected-(U4-I2S_TXD-Pad166)") (class "Default")
      (node (ref "U4") (pin "166") (pinfunction "I2S_TXD_166") (pintype "passive"))
    )
    (net (code "123") (name "unconnected-(U4-REFCLK1+-Pad91)") (class "Default")
      (node (ref "U4") (pin "91") (pinfunction "REFCLK1+_91") (pintype "passive"))
    )
    (net (code "124") (name "unconnected-(U4-REFCLK1--Pad93)") (class "Default")
      (node (ref "U4") (pin "93") (pinfunction "REFCLK1-_93") (pintype "passive"))
    )
    (net (code "125") (name "unconnected-(U4-REFCLK2+-Pad97)") (class "Default")
      (node (ref "U4") (pin "97") (pinfunction "REFCLK2+_97") (pintype "passive"))
    )
    (net (code "126") (name "unconnected-(U4-REFCLK2--Pad99)") (class "Default")
      (node (ref "U4") (pin "99") (pinfunction "REFCLK2-_99") (pintype "passive"))
    )
    (net (code "127") (name "unconnected-(U4-SMB_CLK-Pad106)") (class "Default")
      (node (ref "U4") (pin "106") (pinfunction "SMB_CLK_106") (pintype "passive"))
    )
    (net (code "128") (name "unconnected-(U4-SMB_DATA-Pad108)") (class "Default")
      (node (ref "U4") (pin "108") (pinfunction "SMB_DATA_108") (pintype "passive"))
    )
    (net (code "129") (name "unconnected-(U4-SML1_CLK-Pad147)") (class "Default")
      (node (ref "U4") (pin "147") (pinfunction "SML1_CLK_147") (pintype "passive"))
    )
    (net (code "130") (name "unconnected-(U4-SML1_DATA-Pad145)") (class "Default")
      (node (ref "U4") (pin "145") (pinfunction "SML1_DATA_145") (pintype "passive"))
    )
    (net (code "131") (name "unconnected-(U4-SPI_CLK-Pad155)") (class "Default")
      (node (ref "U4") (pin "155") (pinfunction "SPI_CLK_155") (pintype "passive"))
    )
    (net (code "132") (name "unconnected-(U4-SPI_IO2-Pad161)") (class "Default")
      (node (ref "U4") (pin "161") (pinfunction "SPI_IO2_161") (pintype "passive"))
    )
    (net (code "133") (name "unconnected-(U4-SPI_IO3-Pad153)") (class "Default")
      (node (ref "U4") (pin "153") (pinfunction "SPI_IO3_153") (pintype "passive"))
    )
    (net (code "134") (name "unconnected-(U4-SPI_MISO{slash}SPI_IO1-Pad163)") (class "Default")
      (node (ref "U4") (pin "163") (pinfunction "SPI_MISO/SPI_IO1_163") (pintype "passive"))
    )
    (net (code "135") (name "unconnected-(U4-SPI_MOSI{slash}SPI_IO0-Pad159)") (class "Default")
      (node (ref "U4") (pin "159") (pinfunction "SPI_MOSI/SPI_IO0_159") (pintype "passive"))
    )
    (net (code "136") (name "unconnected-(U4-TCP0_AUX+-Pad223)") (class "Default")
      (node (ref "U4") (pin "223") (pinfunction "TCP0_AUX+_223") (pintype "passive"))
    )
    (net (code "137") (name "unconnected-(U4-TCP0_AUX--Pad221)") (class "Default")
      (node (ref "U4") (pin "221") (pinfunction "TCP0_AUX-_221") (pintype "passive"))
    )
    (net (code "138") (name "unconnected-(U4-TCP0_DDC_SCL-Pad179)") (class "Default")
      (node (ref "U4") (pin "179") (pinfunction "TCP0_DDC_SCL_179") (pintype "passive"))
    )
    (net (code "139") (name "unconnected-(U4-TCP0_DDC_SDA-Pad177)") (class "Default")
      (node (ref "U4") (pin "177") (pinfunction "TCP0_DDC_SDA_177") (pintype "passive"))
    )
    (net (code "140") (name "unconnected-(U4-TCP0_TX0+-Pad247)") (class "Default")
      (node (ref "U4") (pin "247") (pinfunction "TCP0_TX0+_247") (pintype "passive"))
    )
    (net (code "141") (name "unconnected-(U4-TCP0_TX0--Pad245)") (class "Default")
      (node (ref "U4") (pin "245") (pinfunction "TCP0_TX0-_245") (pintype "passive"))
    )
    (net (code "142") (name "unconnected-(U4-TCP0_TX1+-Pad235)") (class "Default")
      (node (ref "U4") (pin "235") (pinfunction "TCP0_TX1+_235") (pintype "passive"))
    )
    (net (code "143") (name "unconnected-(U4-TCP0_TX1--Pad233)") (class "Default")
      (node (ref "U4") (pin "233") (pinfunction "TCP0_TX1-_233") (pintype "passive"))
    )
    (net (code "144") (name "unconnected-(U4-TCP0_TXRX0+-Pad241)") (class "Default")
      (node (ref "U4") (pin "241") (pinfunction "TCP0_TXRX0+_241") (pintype "passive"))
    )
    (net (code "145") (name "unconnected-(U4-TCP0_TXRX0--Pad239)") (class "Default")
      (node (ref "U4") (pin "239") (pinfunction "TCP0_TXRX0-_239") (pintype "passive"))
    )
    (net (code "146") (name "unconnected-(U4-TCP0_TXRX1+-Pad229)") (class "Default")
      (node (ref "U4") (pin "229") (pinfunction "TCP0_TXRX1+_229") (pintype "passive"))
    )
    (net (code "147") (name "unconnected-(U4-TCP0_TXRX1--Pad227)") (class "Default")
      (node (ref "U4") (pin "227") (pinfunction "TCP0_TXRX1-_227") (pintype "passive"))
    )
    (net (code "148") (name "unconnected-(U4-TCP1_AUX+-Pad244)") (class "Default")
      (node (ref "U4") (pin "244") (pinfunction "TCP1_AUX+_244") (pintype "passive"))
    )
    (net (code "149") (name "unconnected-(U4-TCP1_AUX--Pad246)") (class "Default")
      (node (ref "U4") (pin "246") (pinfunction "TCP1_AUX-_246") (pintype "passive"))
    )
    (net (code "150") (name "unconnected-(U4-TCP1_DDC_SCL-Pad175)") (class "Default")
      (node (ref "U4") (pin "175") (pinfunction "TCP1_DDC_SCL_175") (pintype "passive"))
    )
    (net (code "151") (name "unconnected-(U4-TCP1_DDC_SDA-Pad173)") (class "Default")
      (node (ref "U4") (pin "173") (pinfunction "TCP1_DDC_SDA_173") (pintype "passive"))
    )
    (net (code "152") (name "unconnected-(U4-TCP1_HPD-Pad185)") (class "Default")
      (node (ref "U4") (pin "185") (pinfunction "TCP1_HPD_185") (pintype "passive"))
    )
    (net (code "153") (name "unconnected-(U4-TCP1_TX0+-Pad220)") (class "Default")
      (node (ref "U4") (pin "220") (pinfunction "TCP1_TX0+_220") (pintype "passive"))
    )
    (net (code "154") (name "unconnected-(U4-TCP1_TX0--Pad222)") (class "Default")
      (node (ref "U4") (pin "222") (pinfunction "TCP1_TX0-_222") (pintype "passive"))
    )
    (net (code "155") (name "unconnected-(U4-TCP1_TX1+-Pad232)") (class "Default")
      (node (ref "U4") (pin "232") (pinfunction "TCP1_TX1+_232") (pintype "passive"))
    )
    (net (code "156") (name "unconnected-(U4-TCP1_TX1--Pad234)") (class "Default")
      (node (ref "U4") (pin "234") (pinfunction "TCP1_TX1-_234") (pintype "passive"))
    )
    (net (code "157") (name "unconnected-(U4-TCP1_TXRX0+-Pad226)") (class "Default")
      (node (ref "U4") (pin "226") (pinfunction "TCP1_TXRX0+_226") (pintype "passive"))
    )
    (net (code "158") (name "unconnected-(U4-TCP1_TXRX0--Pad228)") (class "Default")
      (node (ref "U4") (pin "228") (pinfunction "TCP1_TXRX0-_228") (pintype "passive"))
    )
    (net (code "159") (name "unconnected-(U4-TCP1_TXRX1+-Pad238)") (class "Default")
      (node (ref "U4") (pin "238") (pinfunction "TCP1_TXRX1+_238") (pintype "passive"))
    )
    (net (code "160") (name "unconnected-(U4-TCP1_TXRX1--Pad240)") (class "Default")
      (node (ref "U4") (pin "240") (pinfunction "TCP1_TXRX1-_240") (pintype "passive"))
    )
    (net (code "161") (name "unconnected-(U4-TPM_IRQ-Pad127)") (class "Default")
      (node (ref "U4") (pin "127") (pinfunction "TPM_IRQ_127") (pintype "passive"))
    )
    (net (code "162") (name "unconnected-(U4-TSENSE-Pad9)") (class "Default")
      (node (ref "U4") (pin "9") (pinfunction "TSENSE_9") (pintype "passive"))
    )
    (net (code "163") (name "unconnected-(U4-UART0_RXD-Pad137)") (class "Default")
      (node (ref "U4") (pin "137") (pinfunction "UART0_RXD_137") (pintype "passive"))
    )
    (net (code "164") (name "unconnected-(U4-UART0_TXD-Pad139)") (class "Default")
      (node (ref "U4") (pin "139") (pinfunction "UART0_TXD_139") (pintype "passive"))
    )
    (net (code "165") (name "unconnected-(U4-UART1_RXD-Pad141)") (class "Default")
      (node (ref "U4") (pin "141") (pinfunction "UART1_RXD_141") (pintype "passive"))
    )
    (net (code "166") (name "unconnected-(U4-UART1_TXD-Pad143)") (class "Default")
      (node (ref "U4") (pin "143") (pinfunction "UART1_TXD_143") (pintype "passive"))
    )
    (net (code "167") (name "unconnected-(U4-UART2_RXD-Pad140)") (class "Default")
      (node (ref "U4") (pin "140") (pinfunction "UART2_RXD_140") (pintype "passive"))
    )
    (net (code "168") (name "unconnected-(U4-UART2_TXD-Pad138)") (class "Default")
      (node (ref "U4") (pin "138") (pinfunction "UART2_TXD_138") (pintype "passive"))
    )
    (net (code "169") (name "unconnected-(U4-USB2_P1+-Pad69)") (class "Default")
      (node (ref "U4") (pin "69") (pinfunction "USB2_P1+_69") (pintype "passive"))
    )
    (net (code "170") (name "unconnected-(U4-USB2_P1--Pad67)") (class "Default")
      (node (ref "U4") (pin "67") (pinfunction "USB2_P1-_67") (pintype "passive"))
    )
    (net (code "171") (name "unconnected-(U4-USB2_P2+-Pad75)") (class "Default")
      (node (ref "U4") (pin "75") (pinfunction "USB2_P2+_75") (pintype "passive"))
    )
    (net (code "172") (name "unconnected-(U4-USB2_P2--Pad73)") (class "Default")
      (node (ref "U4") (pin "73") (pinfunction "USB2_P2-_73") (pintype "passive"))
    )
    (net (code "173") (name "unconnected-(U4-USB2_P3+-Pad81)") (class "Default")
      (node (ref "U4") (pin "81") (pinfunction "USB2_P3+_81") (pintype "passive"))
    )
    (net (code "174") (name "unconnected-(U4-USB2_P3--Pad79)") (class "Default")
      (node (ref "U4") (pin "79") (pinfunction "USB2_P3-_79") (pintype "passive"))
    )
    (net (code "175") (name "unconnected-(U4-USB2_P4+-Pad70)") (class "Default")
      (node (ref "U4") (pin "70") (pinfunction "USB2_P4+_70") (pintype "passive"))
    )
    (net (code "176") (name "unconnected-(U4-USB2_P4--Pad72)") (class "Default")
      (node (ref "U4") (pin "72") (pinfunction "USB2_P4-_72") (pintype "passive"))
    )
    (net (code "177") (name "unconnected-(U4-USB2_P5+-Pad111)") (class "Default")
      (node (ref "U4") (pin "111") (pinfunction "USB2_P5+_111") (pintype "passive"))
    )
    (net (code "178") (name "unconnected-(U4-USB2_P5--Pad109)") (class "Default")
      (node (ref "U4") (pin "109") (pinfunction "USB2_P5-_109") (pintype "passive"))
    )
    (net (code "179") (name "unconnected-(U4-USB2_P6+-Pad112)") (class "Default")
      (node (ref "U4") (pin "112") (pinfunction "USB2_P6+_112") (pintype "passive"))
    )
    (net (code "180") (name "unconnected-(U4-USB2_P6--Pad114)") (class "Default")
      (node (ref "U4") (pin "114") (pinfunction "USB2_P6-_114") (pintype "passive"))
    )
    (net (code "181") (name "unconnected-(U4-USB2_P8+-Pad82)") (class "Default")
      (node (ref "U4") (pin "82") (pinfunction "USB2_P8+_82") (pintype "passive"))
    )
    (net (code "182") (name "unconnected-(U4-USB2_P8--Pad84)") (class "Default")
      (node (ref "U4") (pin "84") (pinfunction "USB2_P8-_84") (pintype "passive"))
    )
    (net (code "183") (name "unconnected-(U4-~{PROCHOT}-Pad117)") (class "Default")
      (node (ref "U4") (pin "117") (pinfunction "~{PROCHOT}_117") (pintype "passive"))
    )
    (net (code "184") (name "unconnected-(U4-~{SMB_ALERT}-Pad104)") (class "Default")
      (node (ref "U4") (pin "104") (pinfunction "~{SMB_ALERT}_104") (pintype "passive"))
    )
    (net (code "185") (name "unconnected-(U4-~{SML1_ALERT}-Pad149)") (class "Default")
      (node (ref "U4") (pin "149") (pinfunction "~{SML1_ALERT}_149") (pintype "passive"))
    )
    (net (code "186") (name "unconnected-(U4-~{SPI_CS2}-Pad157)") (class "Default")
      (node (ref "U4") (pin "157") (pinfunction "~{SPI_CS2}_157") (pintype "passive"))
    )
    (net (code "187") (name "unconnected-(U4-~{SPI_CS}-Pad165)") (class "Default")
      (node (ref "U4") (pin "165") (pinfunction "~{SPI_CS}_165") (pintype "passive"))
    )
    (net (code "188") (name "unconnected-(U4-~{USB_OC}-Pad129)") (class "Default")
      (node (ref "U4") (pin "129") (pinfunction "~{USB_OC}_129") (pintype "passive"))
    )
  )
)
